# goodthopter12.net
KiCad netlist of a schematic drawn in EAGLE
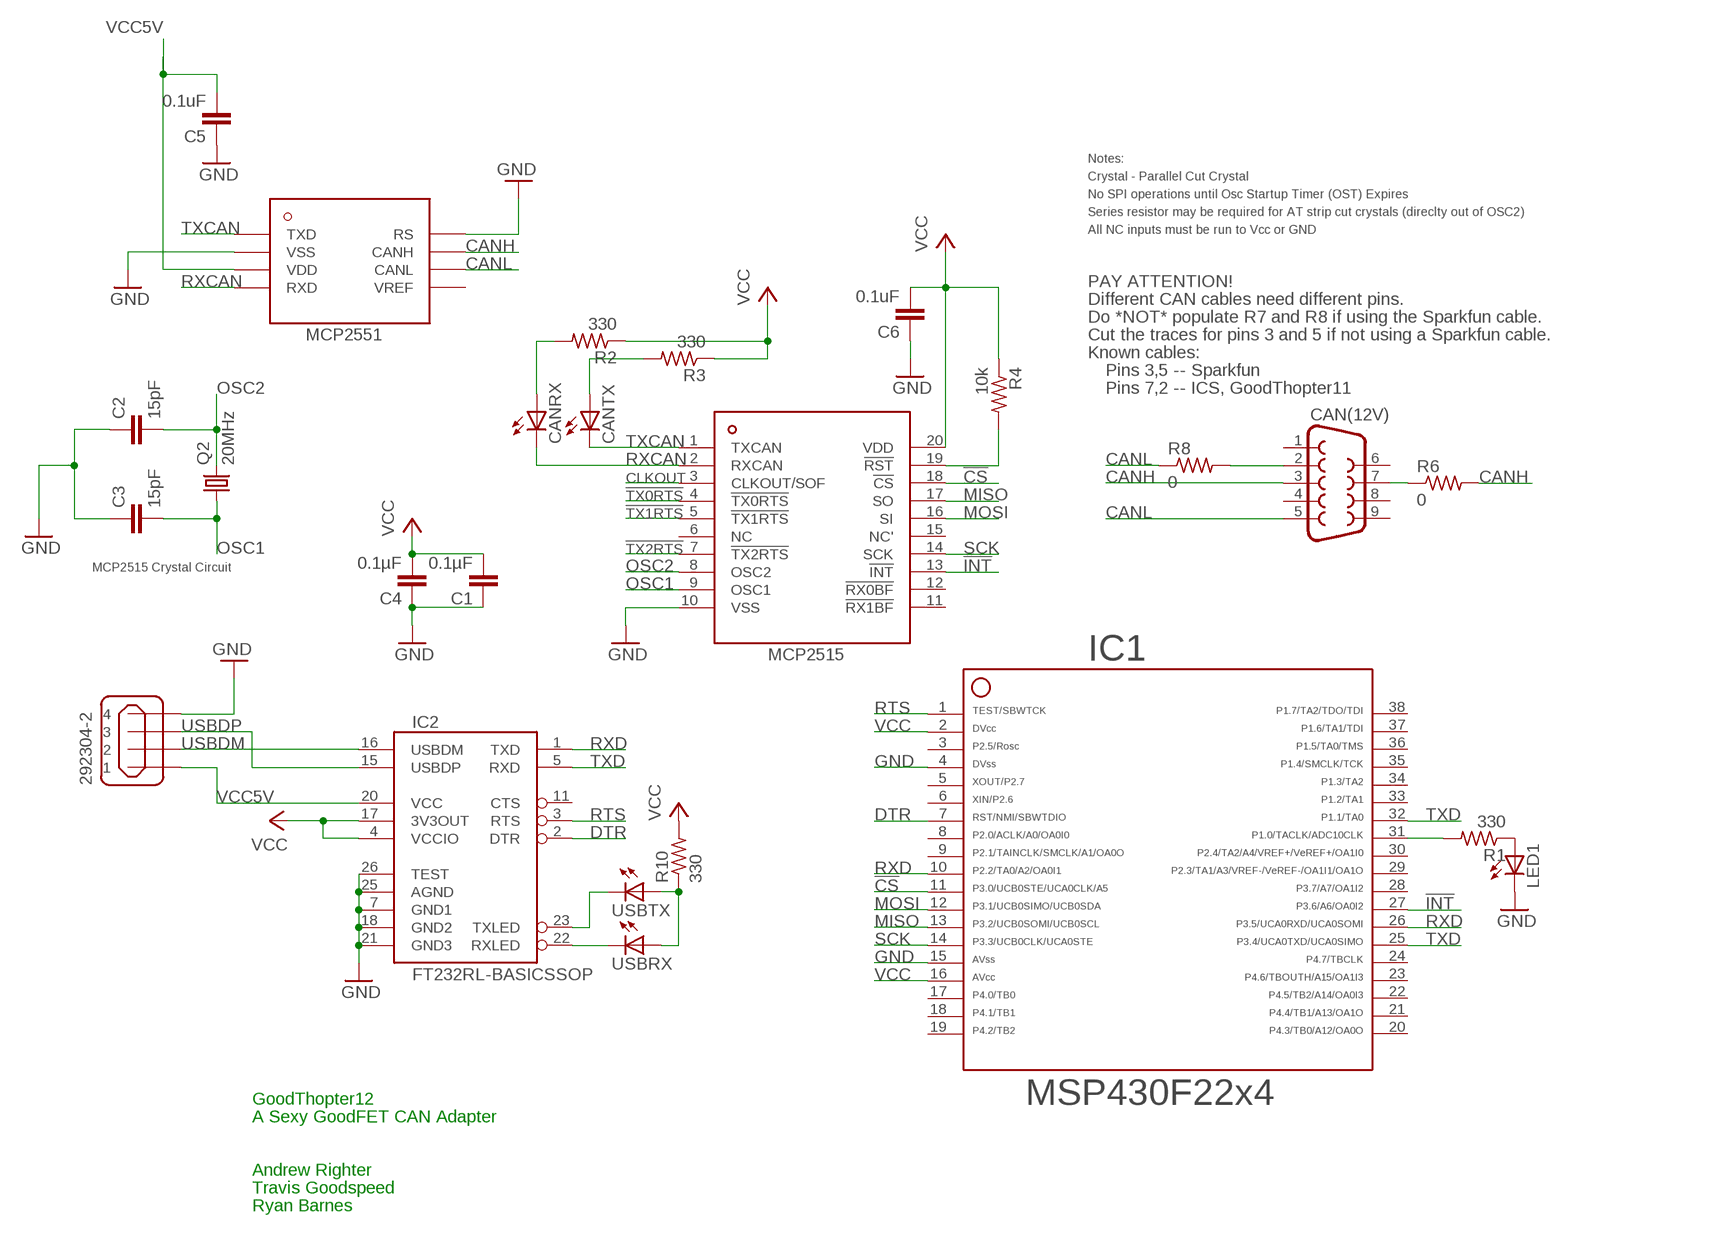
[diagram p0: schematic, sheet 1]

(export (version "E")
  (design (tool "Eeschema 10.0.6"))
  (components
    (comp (ref "292304-2")
      (value "MINI-USB_4P-292304-2")
      (footprint "eagle-import:85-32004-10X")
      (libsource (lib "eagle-import") (part "MINI-USB_4P-292304-2"))
    )
    (comp (ref "C1")
      (value "0.1µF")
      (footprint "eagle-import:C0603")
      (libsource (lib "eagle-import") (part "C-EUC0603"))
    )
    (comp (ref "C2")
      (value "15pF")
      (footprint "eagle-import:C0603")
      (libsource (lib "eagle-import") (part "C-EUC0603"))
    )
    (comp (ref "C3")
      (value "15pF")
      (footprint "eagle-import:C0603")
      (libsource (lib "eagle-import") (part "C-EUC0603"))
    )
    (comp (ref "C4")
      (value "0.1µF")
      (footprint "eagle-import:C0603")
      (libsource (lib "eagle-import") (part "C-EUC0603"))
    )
    (comp (ref "C5")
      (value "0.1uF")
      (footprint "eagle-import:C0603")
      (libsource (lib "eagle-import") (part "C-EUC0603"))
    )
    (comp (ref "C6")
      (value "0.1uF")
      (footprint "eagle-import:C0603")
      (libsource (lib "eagle-import") (part "C-EUC0603"))
    )
    (comp (ref "CAN(12V)")
      (value "DB9MALE")
      (footprint "eagle-import:DB9_MALE")
      (libsource (lib "eagle-import") (part "DB9MALE"))
    )
    (comp (ref "CANRX")
      (value "LEDCHIP-LED0603")
      (footprint "eagle-import:CHIP-LED0603")
      (libsource (lib "eagle-import") (part "LEDCHIP-LED0603"))
    )
    (comp (ref "CANTX")
      (value "LEDCHIP-LED0603")
      (footprint "eagle-import:CHIP-LED0603")
      (libsource (lib "eagle-import") (part "LEDCHIP-LED0603"))
    )
    (comp (ref "IC1")
      (value "F22X4---DA38")
      (footprint "eagle-import:DA38")
      (libsource (lib "eagle-import") (part "F22X4---DA38"))
    )
    (comp (ref "IC2")
      (value "FT232RL-BASICSSOP")
      (footprint "eagle-import:SSOP28DB")
      (libsource (lib "eagle-import") (part "FT232RL-BASICSSOP"))
    )
    (comp (ref "LED1")
      (value "LEDCHIP-LED0603")
      (footprint "eagle-import:CHIP-LED0603")
      (libsource (lib "eagle-import") (part "LEDCHIP-LED0603"))
    )
    (comp (ref "Q2")
      (value "20MHz")
      (footprint "eagle-import:HC49UP")
      (libsource (lib "eagle-import") (part "CRYSTALHC49UP"))
    )
    (comp (ref "R1")
      (value "330")
      (footprint "eagle-import:R0603")
      (libsource (lib "eagle-import") (part "R-US_R0603"))
    )
    (comp (ref "R2")
      (value "330")
      (footprint "eagle-import:R0603")
      (libsource (lib "eagle-import") (part "R-US_R0603"))
    )
    (comp (ref "R3")
      (value "330")
      (footprint "eagle-import:R0603")
      (libsource (lib "eagle-import") (part "R-US_R0603"))
    )
    (comp (ref "R4")
      (value "10k")
      (footprint "eagle-import:R0603")
      (libsource (lib "eagle-import") (part "R-US_R0603"))
    )
    (comp (ref "R6")
      (value "0")
      (footprint "eagle-import:R0603")
      (libsource (lib "eagle-import") (part "R-US_R0603"))
    )
    (comp (ref "R8")
      (value "0")
      (footprint "eagle-import:R0603")
      (libsource (lib "eagle-import") (part "R-US_R0603"))
    )
    (comp (ref "R10")
      (value "330")
      (footprint "eagle-import:R0603")
      (libsource (lib "eagle-import") (part "R-US_R0603"))
    )
    (comp (ref "U$1")
      (value "MCP2515")
      (footprint "eagle-import:TSSOP20")
      (libsource (lib "eagle-import") (part "MCP2515"))
    )
    (comp (ref "U$2")
      (value "MCP2551")
      (footprint "eagle-import:SOIC-8")
      (libsource (lib "eagle-import") (part "MCP2551"))
    )
    (comp (ref "USBRX")
      (value "LEDCHIP-LED0603")
      (footprint "eagle-import:CHIP-LED0603")
      (libsource (lib "eagle-import") (part "LEDCHIP-LED0603"))
    )
    (comp (ref "USBTX")
      (value "LEDCHIP-LED0603")
      (footprint "eagle-import:CHIP-LED0603")
      (libsource (lib "eagle-import") (part "LEDCHIP-LED0603"))
    )
  )
  (nets
    (net (code "1") (name "/CANH") (class "Default")
      (node (ref "CAN(12V)") (pin "3") (pinfunction "3_3") (pintype "passive"))
      (node (ref "R6") (pin "2") (pinfunction "2_2") (pintype "passive"))
      (node (ref "U$2") (pin "CANH") (pinfunction "CANH_CANH") (pintype "bidirectional"))
    )
    (net (code "2") (name "/CANL") (class "Default")
      (node (ref "CAN(12V)") (pin "5") (pinfunction "5_5") (pintype "passive"))
      (node (ref "R8") (pin "1") (pinfunction "1_1") (pintype "passive"))
      (node (ref "U$2") (pin "CANL") (pinfunction "CANL_CANL") (pintype "bidirectional"))
    )
    (net (code "3") (name "/CLKOUT") (class "Default")
      (node (ref "U$1") (pin "3") (pinfunction "CLKOUT/SOF_3") (pintype "bidirectional"))
    )
    (net (code "4") (name "/DTR") (class "Default")
      (node (ref "IC1") (pin "7") (pinfunction "7_7") (pintype "bidirectional"))
      (node (ref "IC2") (pin "2") (pinfunction "DTR_2") (pintype "bidirectional"))
    )
    (net (code "5") (name "/MISO") (class "Default")
      (node (ref "IC1") (pin "13") (pinfunction "13_13") (pintype "bidirectional"))
      (node (ref "U$1") (pin "17") (pinfunction "SO_17") (pintype "bidirectional"))
    )
    (net (code "6") (name "/MOSI") (class "Default")
      (node (ref "IC1") (pin "12") (pinfunction "12_12") (pintype "bidirectional"))
      (node (ref "U$1") (pin "16") (pinfunction "SI_16") (pintype "bidirectional"))
    )
    (net (code "7") (name "/OSC1") (class "Default")
      (node (ref "C3") (pin "2") (pinfunction "2_2") (pintype "passive"))
      (node (ref "Q2") (pin "1") (pinfunction "1_1") (pintype "passive"))
      (node (ref "U$1") (pin "9") (pinfunction "OSC1_9") (pintype "bidirectional"))
    )
    (net (code "8") (name "/OSC2") (class "Default")
      (node (ref "C2") (pin "2") (pinfunction "2_2") (pintype "passive"))
      (node (ref "Q2") (pin "2") (pinfunction "2_2") (pintype "passive"))
      (node (ref "U$1") (pin "8") (pinfunction "OSC2_8") (pintype "bidirectional"))
    )
    (net (code "9") (name "/RTS") (class "Default")
      (node (ref "IC1") (pin "1") (pinfunction "1_1") (pintype "input"))
      (node (ref "IC2") (pin "3") (pinfunction "RTS_3") (pintype "bidirectional"))
    )
    (net (code "10") (name "/RXCAN") (class "Default")
      (node (ref "CANRX") (pin "C") (pinfunction "C_C") (pintype "passive"))
      (node (ref "U$1") (pin "2") (pinfunction "RXCAN_2") (pintype "bidirectional"))
      (node (ref "U$2") (pin "RXD") (pinfunction "RXD_RXD") (pintype "bidirectional"))
    )
    (net (code "11") (name "/RXD") (class "Default")
      (node (ref "IC1") (pin "10") (pinfunction "10_10") (pintype "bidirectional"))
      (node (ref "IC1") (pin "26") (pinfunction "26_26") (pintype "bidirectional"))
      (node (ref "IC2") (pin "1") (pinfunction "TXD_1") (pintype "output"))
    )
    (net (code "12") (name "/SCK") (class "Default")
      (node (ref "IC1") (pin "14") (pinfunction "14_14") (pintype "bidirectional"))
      (node (ref "U$1") (pin "14") (pinfunction "SCK_14") (pintype "bidirectional"))
    )
    (net (code "13") (name "/TXCAN") (class "Default")
      (node (ref "CANTX") (pin "C") (pinfunction "C_C") (pintype "passive"))
      (node (ref "U$1") (pin "1") (pinfunction "TXCAN_1") (pintype "bidirectional"))
      (node (ref "U$2") (pin "TXD") (pinfunction "TXD_TXD") (pintype "bidirectional"))
    )
    (net (code "14") (name "/TXD") (class "Default")
      (node (ref "IC1") (pin "25") (pinfunction "25_25") (pintype "bidirectional"))
      (node (ref "IC1") (pin "32") (pinfunction "32_32") (pintype "bidirectional"))
      (node (ref "IC2") (pin "5") (pinfunction "RXD_5") (pintype "input"))
    )
    (net (code "15") (name "/USBDM") (class "Default")
      (node (ref "292304-2") (pin "2") (pinfunction "2_2") (pintype "passive"))
      (node (ref "IC2") (pin "16") (pinfunction "USBDM_16") (pintype "bidirectional"))
    )
    (net (code "16") (name "/USBDP") (class "Default")
      (node (ref "292304-2") (pin "3") (pinfunction "3_3") (pintype "passive"))
      (node (ref "IC2") (pin "15") (pinfunction "USBDP_15") (pintype "bidirectional"))
    )
    (net (code "17") (name "/VCC5V") (class "Default")
      (node (ref "292304-2") (pin "1") (pinfunction "1_1") (pintype "passive"))
      (node (ref "C5") (pin "2") (pinfunction "2_2") (pintype "passive"))
      (node (ref "IC2") (pin "20") (pinfunction "VCC_20") (pintype "power_in"))
      (node (ref "U$2") (pin "VDD") (pinfunction "VDD_VDD") (pintype "bidirectional"))
    )
    (net (code "18") (name "/~{CS}") (class "Default")
      (node (ref "IC1") (pin "11") (pinfunction "11_11") (pintype "bidirectional"))
      (node (ref "U$1") (pin "18") (pinfunction "~{CS}_18") (pintype "bidirectional"))
    )
    (net (code "19") (name "/~{INT}") (class "Default")
      (node (ref "IC1") (pin "27") (pinfunction "27_27") (pintype "bidirectional"))
      (node (ref "U$1") (pin "13") (pinfunction "~{INT}_13") (pintype "bidirectional"))
    )
    (net (code "20") (name "/~{TX0RTS}") (class "Default")
      (node (ref "U$1") (pin "4") (pinfunction "~{TX0RTS}_4") (pintype "bidirectional"))
    )
    (net (code "21") (name "/~{TX1RTS}") (class "Default")
      (node (ref "U$1") (pin "5") (pinfunction "~{TX1RTS}_5") (pintype "bidirectional"))
    )
    (net (code "22") (name "/~{TX2RTS}") (class "Default")
      (node (ref "U$1") (pin "7") (pinfunction "~{TX2RTS}_7") (pintype "bidirectional"))
    )
    (net (code "23") (name "GND") (class "Default")
      (node (ref "292304-2") (pin "4") (pinfunction "4_4") (pintype "passive"))
      (node (ref "C1") (pin "1") (pinfunction "1_1") (pintype "passive"))
      (node (ref "C2") (pin "1") (pinfunction "1_1") (pintype "passive"))
      (node (ref "C3") (pin "1") (pinfunction "1_1") (pintype "passive"))
      (node (ref "C4") (pin "1") (pinfunction "1_1") (pintype "passive"))
      (node (ref "C5") (pin "1") (pinfunction "1_1") (pintype "passive"))
      (node (ref "C6") (pin "1") (pinfunction "1_1") (pintype "passive"))
      (node (ref "IC1") (pin "15") (pinfunction "15_15") (pintype "power_in"))
      (node (ref "IC1") (pin "4") (pinfunction "4_4") (pintype "power_in"))
      (node (ref "IC2") (pin "18") (pinfunction "GND2_18") (pintype "power_in"))
      (node (ref "IC2") (pin "21") (pinfunction "GND3_21") (pintype "power_in"))
      (node (ref "IC2") (pin "25") (pinfunction "AGND_25") (pintype "power_in"))
      (node (ref "IC2") (pin "26") (pinfunction "TEST_26") (pintype "input"))
      (node (ref "IC2") (pin "7") (pinfunction "GND1_7") (pintype "power_in"))
      (node (ref "LED1") (pin "C") (pinfunction "C_C") (pintype "passive"))
      (node (ref "U$1") (pin "10") (pinfunction "VSS_10") (pintype "bidirectional"))
      (node (ref "U$2") (pin "RS") (pinfunction "RS_RS") (pintype "bidirectional"))
      (node (ref "U$2") (pin "VSS") (pinfunction "VSS_VSS") (pintype "bidirectional"))
    )
    (net (code "24") (name "Net-(CAN(12V)-Pad2)") (class "Default")
      (node (ref "CAN(12V)") (pin "2") (pinfunction "2_2") (pintype "passive"))
      (node (ref "R8") (pin "2") (pinfunction "2_2") (pintype "passive"))
    )
    (net (code "25") (name "Net-(CAN(12V)-Pad7)") (class "Default")
      (node (ref "CAN(12V)") (pin "7") (pinfunction "7_7") (pintype "passive"))
      (node (ref "R6") (pin "1") (pinfunction "1_1") (pintype "passive"))
    )
    (net (code "26") (name "Net-(CANRX-PadA)") (class "Default")
      (node (ref "CANRX") (pin "A") (pinfunction "A_A") (pintype "passive"))
      (node (ref "R2") (pin "2") (pinfunction "2_2") (pintype "passive"))
    )
    (net (code "27") (name "Net-(CANTX-PadA)") (class "Default")
      (node (ref "CANTX") (pin "A") (pinfunction "A_A") (pintype "passive"))
      (node (ref "R3") (pin "2") (pinfunction "2_2") (pintype "passive"))
    )
    (net (code "28") (name "Net-(IC1-Pad31)") (class "Default")
      (node (ref "IC1") (pin "31") (pinfunction "31_31") (pintype "bidirectional"))
      (node (ref "R1") (pin "2") (pinfunction "2_2") (pintype "passive"))
    )
    (net (code "29") (name "Net-(IC2-RXLED)") (class "Default")
      (node (ref "IC2") (pin "22") (pinfunction "RXLED_22") (pintype "bidirectional"))
      (node (ref "USBRX") (pin "C") (pinfunction "C_C") (pintype "passive"))
    )
    (net (code "30") (name "Net-(IC2-TXLED)") (class "Default")
      (node (ref "IC2") (pin "23") (pinfunction "TXLED_23") (pintype "bidirectional"))
      (node (ref "USBTX") (pin "C") (pinfunction "C_C") (pintype "passive"))
    )
    (net (code "31") (name "Net-(LED1-PadA)") (class "Default")
      (node (ref "LED1") (pin "A") (pinfunction "A_A") (pintype "passive"))
      (node (ref "R1") (pin "1") (pinfunction "1_1") (pintype "passive"))
    )
    (net (code "32") (name "Net-(R10-Pad1)") (class "Default")
      (node (ref "R10") (pin "1") (pinfunction "1_1") (pintype "passive"))
      (node (ref "USBRX") (pin "A") (pinfunction "A_A") (pintype "passive"))
      (node (ref "USBTX") (pin "A") (pinfunction "A_A") (pintype "passive"))
    )
    (net (code "33") (name "Net-(U$1-~{RST})") (class "Default")
      (node (ref "R4") (pin "2") (pinfunction "2_2") (pintype "passive"))
      (node (ref "U$1") (pin "19") (pinfunction "~{RST}_19") (pintype "bidirectional"))
    )
    (net (code "34") (name "VCC") (class "Default")
      (node (ref "C1") (pin "2") (pinfunction "2_2") (pintype "passive"))
      (node (ref "C4") (pin "2") (pinfunction "2_2") (pintype "passive"))
      (node (ref "C6") (pin "2") (pinfunction "2_2") (pintype "passive"))
      (node (ref "IC1") (pin "16") (pinfunction "16_16") (pintype "power_in"))
      (node (ref "IC1") (pin "2") (pinfunction "2_2") (pintype "power_in"))
      (node (ref "IC2") (pin "17") (pinfunction "3V3OUT_17") (pintype "output"))
      (node (ref "IC2") (pin "4") (pinfunction "VCCIO_4") (pintype "power_in"))
      (node (ref "R10") (pin "2") (pinfunction "2_2") (pintype "passive"))
      (node (ref "R2") (pin "1") (pinfunction "1_1") (pintype "passive"))
      (node (ref "R3") (pin "1") (pinfunction "1_1") (pintype "passive"))
      (node (ref "R4") (pin "1") (pinfunction "1_1") (pintype "passive"))
      (node (ref "U$1") (pin "20") (pinfunction "VDD_20") (pintype "bidirectional"))
    )
    (net (code "35") (name "unconnected-(CAN(12V)-Pad1)") (class "Default")
      (node (ref "CAN(12V)") (pin "1") (pinfunction "1_1") (pintype "passive"))
    )
    (net (code "36") (name "unconnected-(CAN(12V)-Pad4)") (class "Default")
      (node (ref "CAN(12V)") (pin "4") (pinfunction "4_4") (pintype "passive"))
    )
    (net (code "37") (name "unconnected-(CAN(12V)-Pad6)") (class "Default")
      (node (ref "CAN(12V)") (pin "6") (pinfunction "6_6") (pintype "passive"))
    )
    (net (code "38") (name "unconnected-(CAN(12V)-Pad8)") (class "Default")
      (node (ref "CAN(12V)") (pin "8") (pinfunction "8_8") (pintype "passive"))
    )
    (net (code "39") (name "unconnected-(CAN(12V)-Pad9)") (class "Default")
      (node (ref "CAN(12V)") (pin "9") (pinfunction "9_9") (pintype "passive"))
    )
    (net (code "40") (name "unconnected-(IC1-Pad3)") (class "Default")
      (node (ref "IC1") (pin "3") (pinfunction "3_3") (pintype "bidirectional"))
    )
    (net (code "41") (name "unconnected-(IC1-Pad5)") (class "Default")
      (node (ref "IC1") (pin "5") (pinfunction "5_5") (pintype "bidirectional"))
    )
    (net (code "42") (name "unconnected-(IC1-Pad6)") (class "Default")
      (node (ref "IC1") (pin "6") (pinfunction "6_6") (pintype "bidirectional"))
    )
    (net (code "43") (name "unconnected-(IC1-Pad8)") (class "Default")
      (node (ref "IC1") (pin "8") (pinfunction "8_8") (pintype "bidirectional"))
    )
    (net (code "44") (name "unconnected-(IC1-Pad9)") (class "Default")
      (node (ref "IC1") (pin "9") (pinfunction "9_9") (pintype "bidirectional"))
    )
    (net (code "45") (name "unconnected-(IC1-Pad17)") (class "Default")
      (node (ref "IC1") (pin "17") (pinfunction "17_17") (pintype "bidirectional"))
    )
    (net (code "46") (name "unconnected-(IC1-Pad18)") (class "Default")
      (node (ref "IC1") (pin "18") (pinfunction "18_18") (pintype "bidirectional"))
    )
    (net (code "47") (name "unconnected-(IC1-Pad19)") (class "Default")
      (node (ref "IC1") (pin "19") (pinfunction "19_19") (pintype "bidirectional"))
    )
    (net (code "48") (name "unconnected-(IC1-Pad20)") (class "Default")
      (node (ref "IC1") (pin "20") (pinfunction "20_20") (pintype "bidirectional"))
    )
    (net (code "49") (name "unconnected-(IC1-Pad21)") (class "Default")
      (node (ref "IC1") (pin "21") (pinfunction "21_21") (pintype "bidirectional"))
    )
    (net (code "50") (name "unconnected-(IC1-Pad22)") (class "Default")
      (node (ref "IC1") (pin "22") (pinfunction "22_22") (pintype "bidirectional"))
    )
    (net (code "51") (name "unconnected-(IC1-Pad23)") (class "Default")
      (node (ref "IC1") (pin "23") (pinfunction "23_23") (pintype "bidirectional"))
    )
    (net (code "52") (name "unconnected-(IC1-Pad24)") (class "Default")
      (node (ref "IC1") (pin "24") (pinfunction "24_24") (pintype "bidirectional"))
    )
    (net (code "53") (name "unconnected-(IC1-Pad28)") (class "Default")
      (node (ref "IC1") (pin "28") (pinfunction "28_28") (pintype "bidirectional"))
    )
    (net (code "54") (name "unconnected-(IC1-Pad29)") (class "Default")
      (node (ref "IC1") (pin "29") (pinfunction "29_29") (pintype "bidirectional"))
    )
    (net (code "55") (name "unconnected-(IC1-Pad30)") (class "Default")
      (node (ref "IC1") (pin "30") (pinfunction "30_30") (pintype "bidirectional"))
    )
    (net (code "56") (name "unconnected-(IC1-Pad33)") (class "Default")
      (node (ref "IC1") (pin "33") (pinfunction "33_33") (pintype "bidirectional"))
    )
    (net (code "57") (name "unconnected-(IC1-Pad34)") (class "Default")
      (node (ref "IC1") (pin "34") (pinfunction "34_34") (pintype "bidirectional"))
    )
    (net (code "58") (name "unconnected-(IC1-Pad35)") (class "Default")
      (node (ref "IC1") (pin "35") (pinfunction "35_35") (pintype "bidirectional"))
    )
    (net (code "59") (name "unconnected-(IC1-Pad36)") (class "Default")
      (node (ref "IC1") (pin "36") (pinfunction "36_36") (pintype "bidirectional"))
    )
    (net (code "60") (name "unconnected-(IC1-Pad37)") (class "Default")
      (node (ref "IC1") (pin "37") (pinfunction "37_37") (pintype "bidirectional"))
    )
    (net (code "61") (name "unconnected-(IC1-Pad38)") (class "Default")
      (node (ref "IC1") (pin "38") (pinfunction "38_38") (pintype "bidirectional"))
    )
    (net (code "62") (name "unconnected-(IC2-CTS-Pad11)") (class "Default")
      (node (ref "IC2") (pin "11") (pinfunction "CTS_11") (pintype "bidirectional"))
    )
    (net (code "63") (name "unconnected-(U$1-NC'-Pad15)") (class "Default")
      (node (ref "U$1") (pin "15") (pinfunction "NC'_15") (pintype "bidirectional"))
    )
    (net (code "64") (name "unconnected-(U$1-NC-Pad6)") (class "Default")
      (node (ref "U$1") (pin "6") (pinfunction "NC_6") (pintype "bidirectional"))
    )
    (net (code "65") (name "unconnected-(U$1-~{RX0BF}-Pad12)") (class "Default")
      (node (ref "U$1") (pin "12") (pinfunction "~{RX0BF}_12") (pintype "bidirectional"))
    )
    (net (code "66") (name "unconnected-(U$1-~{RX1BF}-Pad11)") (class "Default")
      (node (ref "U$1") (pin "11") (pinfunction "~{RX1BF}_11") (pintype "bidirectional"))
    )
    (net (code "67") (name "unconnected-(U$2-PadVREF)") (class "Default")
      (node (ref "U$2") (pin "VREF") (pinfunction "VREF_VREF") (pintype "bidirectional"))
    )
  )
)
